# CGScale.net
KiCad netlist of a schematic drawn in EAGLE
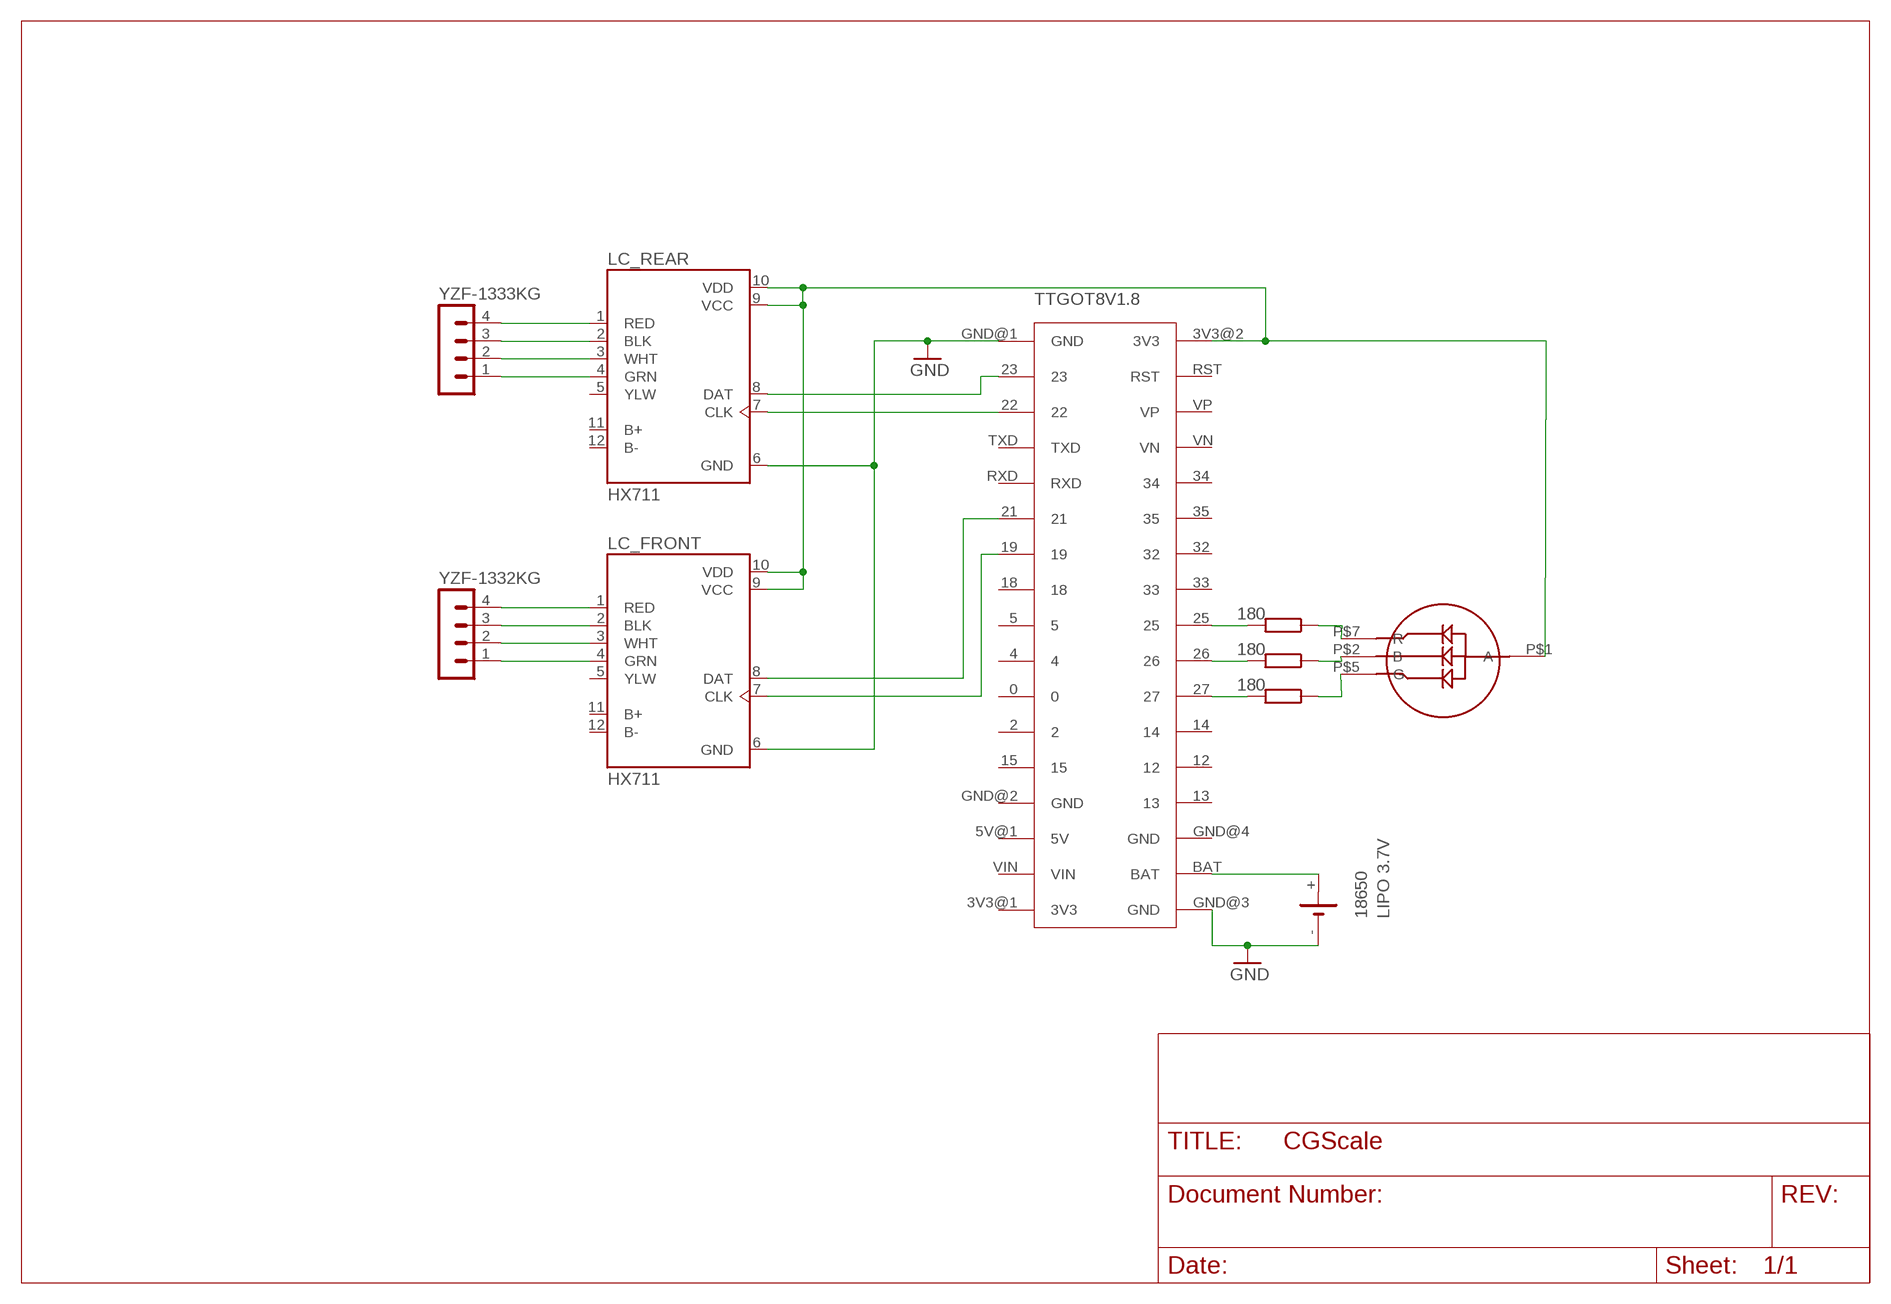
[diagram p0: schematic, sheet 1]

(export (version "E")
  (design (tool "Eeschema 10.0.6"))
  (components
    (comp (ref "18650")
      (value "LIPO 3.7V")
      (footprint "eagle-import:SL-150-1_2AA_PR")
      (libsource (lib "eagle-import") (part "SL-150-1/2AA/PR"))
    )
    (comp (ref "LC_FRONT")
      (value "HX711")
      (footprint "eagle-import:SPARKFUN_SEN-13879")
      (fields (field (name "MF") "SparkFun") (field (name "MP") "SEN-13879"))
      (libsource (lib "eagle-import") (part "SEN-13879"))
    )
    (comp (ref "LC_REAR")
      (value "HX711")
      (footprint "eagle-import:SPARKFUN_SEN-13879")
      (fields (field (name "MF") "SparkFun") (field (name "MP") "SEN-13879"))
      (libsource (lib "eagle-import") (part "SEN-13879"))
    )
    (comp (ref "RGB_LED")
      (value "LED-4_PIN")
      (footprint "eagle-import:LED-4_PIN")
      (libsource (lib "eagle-import") (part "LED-4_PIN"))
    )
    (comp (ref "TTGOT8V1.8")
      (value "TTGO-T8_V18")
      (footprint "eagle-import:TTGO-T8_V18")
      (libsource (lib "eagle-import") (part "TTGO-T8_V18"))
    )
    (comp (ref "YZF-1332KG")
      (value "MA04-1")
      (footprint "eagle-import:MA04-1")
      (libsource (lib "eagle-import") (part "MA04-1"))
    )
    (comp (ref "YZF-1333KG")
      (value "MA04-1")
      (footprint "eagle-import:MA04-1")
      (libsource (lib "eagle-import") (part "MA04-1"))
    )
  )
  (nets
    (net (code "1") (name "GND") (class "Default")
      (node (ref "18650") (pin "-") (pinfunction "-_-") (pintype "passive"))
      (node (ref "LC_FRONT") (pin "6") (pinfunction "GND_6") (pintype "power_in"))
      (node (ref "LC_REAR") (pin "6") (pinfunction "GND_6") (pintype "power_in"))
      (node (ref "TTGOT8V1.8") (pin "GND@1") (pinfunction "GND_GND@1") (pintype "bidirectional"))
      (node (ref "TTGOT8V1.8") (pin "GND@3") (pinfunction "GND_GND@3") (pintype "bidirectional"))
    )
    (net (code "2") (name "Net-(18650-Pad+)") (class "Default")
      (node (ref "18650") (pin "+") (pinfunction "+_+") (pintype "passive"))
      (node (ref "TTGOT8V1.8") (pin "BAT") (pinfunction "BAT_BAT") (pintype "bidirectional"))
    )
    (net (code "3") (name "Net-(LC_FRONT-BLK)") (class "Default")
      (node (ref "LC_FRONT") (pin "2") (pinfunction "BLK_2") (pintype "bidirectional"))
      (node (ref "YZF-1332KG") (pin "3") (pinfunction "3_3") (pintype "passive"))
    )
    (net (code "4") (name "Net-(LC_FRONT-CLK)") (class "Default")
      (node (ref "LC_FRONT") (pin "7") (pinfunction "CLK_7") (pintype "input"))
      (node (ref "TTGOT8V1.8") (pin "19") (pinfunction "19_19") (pintype "bidirectional"))
    )
    (net (code "5") (name "Net-(LC_FRONT-DAT)") (class "Default")
      (node (ref "LC_FRONT") (pin "8") (pinfunction "DAT_8") (pintype "output"))
      (node (ref "TTGOT8V1.8") (pin "21") (pinfunction "21_21") (pintype "bidirectional"))
    )
    (net (code "6") (name "Net-(LC_FRONT-GRN)") (class "Default")
      (node (ref "LC_FRONT") (pin "4") (pinfunction "GRN_4") (pintype "input"))
      (node (ref "YZF-1332KG") (pin "1") (pinfunction "1_1") (pintype "passive"))
    )
    (net (code "7") (name "Net-(LC_FRONT-RED)") (class "Default")
      (node (ref "LC_FRONT") (pin "1") (pinfunction "RED_1") (pintype "bidirectional"))
      (node (ref "YZF-1332KG") (pin "4") (pinfunction "4_4") (pintype "passive"))
    )
    (net (code "8") (name "Net-(LC_FRONT-VCC)") (class "Default")
      (node (ref "LC_FRONT") (pin "10") (pinfunction "VDD_10") (pintype "power_in"))
      (node (ref "LC_FRONT") (pin "9") (pinfunction "VCC_9") (pintype "power_in"))
      (node (ref "LC_REAR") (pin "10") (pinfunction "VDD_10") (pintype "power_in"))
      (node (ref "LC_REAR") (pin "9") (pinfunction "VCC_9") (pintype "power_in"))
      (node (ref "RGB_LED") (pin "P$1") (pinfunction "A_P$1") (pintype "bidirectional"))
      (node (ref "TTGOT8V1.8") (pin "3V3@2") (pinfunction "3V3_3V3@2") (pintype "bidirectional"))
    )
    (net (code "9") (name "Net-(LC_FRONT-WHT)") (class "Default")
      (node (ref "LC_FRONT") (pin "3") (pinfunction "WHT_3") (pintype "input"))
      (node (ref "YZF-1332KG") (pin "2") (pinfunction "2_2") (pintype "passive"))
    )
    (net (code "10") (name "Net-(LC_REAR-BLK)") (class "Default")
      (node (ref "LC_REAR") (pin "2") (pinfunction "BLK_2") (pintype "bidirectional"))
      (node (ref "YZF-1333KG") (pin "3") (pinfunction "3_3") (pintype "passive"))
    )
    (net (code "11") (name "Net-(LC_REAR-CLK)") (class "Default")
      (node (ref "LC_REAR") (pin "7") (pinfunction "CLK_7") (pintype "input"))
      (node (ref "TTGOT8V1.8") (pin "22") (pinfunction "22_22") (pintype "bidirectional"))
    )
    (net (code "12") (name "Net-(LC_REAR-DAT)") (class "Default")
      (node (ref "LC_REAR") (pin "8") (pinfunction "DAT_8") (pintype "output"))
      (node (ref "TTGOT8V1.8") (pin "23") (pinfunction "23_23") (pintype "bidirectional"))
    )
    (net (code "13") (name "Net-(LC_REAR-GRN)") (class "Default")
      (node (ref "LC_REAR") (pin "4") (pinfunction "GRN_4") (pintype "input"))
      (node (ref "YZF-1333KG") (pin "1") (pinfunction "1_1") (pintype "passive"))
    )
    (net (code "14") (name "Net-(LC_REAR-RED)") (class "Default")
      (node (ref "LC_REAR") (pin "1") (pinfunction "RED_1") (pintype "bidirectional"))
      (node (ref "YZF-1333KG") (pin "4") (pinfunction "4_4") (pintype "passive"))
    )
    (net (code "15") (name "Net-(LC_REAR-WHT)") (class "Default")
      (node (ref "LC_REAR") (pin "3") (pinfunction "WHT_3") (pintype "input"))
      (node (ref "YZF-1333KG") (pin "2") (pinfunction "2_2") (pintype "passive"))
    )
    (net (code "16") (name "unconnected-(LC_FRONT-B+-Pad11)") (class "Default")
      (node (ref "LC_FRONT") (pin "11") (pinfunction "B+_11") (pintype "input"))
    )
    (net (code "17") (name "unconnected-(LC_FRONT-B--Pad12)") (class "Default")
      (node (ref "LC_FRONT") (pin "12") (pinfunction "B-_12") (pintype "input"))
    )
    (net (code "18") (name "unconnected-(LC_FRONT-YLW-Pad5)") (class "Default")
      (node (ref "LC_FRONT") (pin "5") (pinfunction "YLW_5") (pintype "bidirectional"))
    )
    (net (code "19") (name "unconnected-(LC_REAR-B+-Pad11)") (class "Default")
      (node (ref "LC_REAR") (pin "11") (pinfunction "B+_11") (pintype "input"))
    )
    (net (code "20") (name "unconnected-(LC_REAR-B--Pad12)") (class "Default")
      (node (ref "LC_REAR") (pin "12") (pinfunction "B-_12") (pintype "input"))
    )
    (net (code "21") (name "unconnected-(LC_REAR-YLW-Pad5)") (class "Default")
      (node (ref "LC_REAR") (pin "5") (pinfunction "YLW_5") (pintype "bidirectional"))
    )
    (net (code "22") (name "unconnected-(RGB_LED-B-PadP$2)") (class "Default")
      (node (ref "RGB_LED") (pin "P$2") (pinfunction "B_P$2") (pintype "bidirectional"))
    )
    (net (code "23") (name "unconnected-(RGB_LED-G-PadP$5)") (class "Default")
      (node (ref "RGB_LED") (pin "P$5") (pinfunction "G_P$5") (pintype "bidirectional"))
    )
    (net (code "24") (name "unconnected-(RGB_LED-R-PadP$7)") (class "Default")
      (node (ref "RGB_LED") (pin "P$7") (pinfunction "R_P$7") (pintype "bidirectional"))
    )
    (net (code "25") (name "unconnected-(TTGOT8V1.8-3V3-Pad3V3@1)") (class "Default")
      (node (ref "TTGOT8V1.8") (pin "3V3@1") (pinfunction "3V3_3V3@1") (pintype "bidirectional"))
    )
    (net (code "26") (name "unconnected-(TTGOT8V1.8-5V-Pad5V@1)") (class "Default")
      (node (ref "TTGOT8V1.8") (pin "5V@1") (pinfunction "5V_5V@1") (pintype "bidirectional"))
    )
    (net (code "27") (name "unconnected-(TTGOT8V1.8-GND-PadGND@2)") (class "Default")
      (node (ref "TTGOT8V1.8") (pin "GND@2") (pinfunction "GND_GND@2") (pintype "bidirectional"))
    )
    (net (code "28") (name "unconnected-(TTGOT8V1.8-GND-PadGND@4)") (class "Default")
      (node (ref "TTGOT8V1.8") (pin "GND@4") (pinfunction "GND_GND@4") (pintype "bidirectional"))
    )
    (net (code "29") (name "unconnected-(TTGOT8V1.8-Pad0)") (class "Default")
      (node (ref "TTGOT8V1.8") (pin "0") (pinfunction "0_0") (pintype "bidirectional"))
    )
    (net (code "30") (name "unconnected-(TTGOT8V1.8-Pad2)") (class "Default")
      (node (ref "TTGOT8V1.8") (pin "2") (pinfunction "2_2") (pintype "bidirectional"))
    )
    (net (code "31") (name "unconnected-(TTGOT8V1.8-Pad4)") (class "Default")
      (node (ref "TTGOT8V1.8") (pin "4") (pinfunction "4_4") (pintype "bidirectional"))
    )
    (net (code "32") (name "unconnected-(TTGOT8V1.8-Pad5)") (class "Default")
      (node (ref "TTGOT8V1.8") (pin "5") (pinfunction "5_5") (pintype "bidirectional"))
    )
    (net (code "33") (name "unconnected-(TTGOT8V1.8-Pad12)") (class "Default")
      (node (ref "TTGOT8V1.8") (pin "12") (pinfunction "12_12") (pintype "bidirectional"))
    )
    (net (code "34") (name "unconnected-(TTGOT8V1.8-Pad13)") (class "Default")
      (node (ref "TTGOT8V1.8") (pin "13") (pinfunction "13_13") (pintype "bidirectional"))
    )
    (net (code "35") (name "unconnected-(TTGOT8V1.8-Pad14)") (class "Default")
      (node (ref "TTGOT8V1.8") (pin "14") (pinfunction "14_14") (pintype "bidirectional"))
    )
    (net (code "36") (name "unconnected-(TTGOT8V1.8-Pad15)") (class "Default")
      (node (ref "TTGOT8V1.8") (pin "15") (pinfunction "15_15") (pintype "bidirectional"))
    )
    (net (code "37") (name "unconnected-(TTGOT8V1.8-Pad18)") (class "Default")
      (node (ref "TTGOT8V1.8") (pin "18") (pinfunction "18_18") (pintype "bidirectional"))
    )
    (net (code "38") (name "unconnected-(TTGOT8V1.8-Pad25)") (class "Default")
      (node (ref "TTGOT8V1.8") (pin "25") (pinfunction "25_25") (pintype "bidirectional"))
    )
    (net (code "39") (name "unconnected-(TTGOT8V1.8-Pad26)") (class "Default")
      (node (ref "TTGOT8V1.8") (pin "26") (pinfunction "26_26") (pintype "bidirectional"))
    )
    (net (code "40") (name "unconnected-(TTGOT8V1.8-Pad27)") (class "Default")
      (node (ref "TTGOT8V1.8") (pin "27") (pinfunction "27_27") (pintype "bidirectional"))
    )
    (net (code "41") (name "unconnected-(TTGOT8V1.8-Pad32)") (class "Default")
      (node (ref "TTGOT8V1.8") (pin "32") (pinfunction "32_32") (pintype "bidirectional"))
    )
    (net (code "42") (name "unconnected-(TTGOT8V1.8-Pad33)") (class "Default")
      (node (ref "TTGOT8V1.8") (pin "33") (pinfunction "33_33") (pintype "bidirectional"))
    )
    (net (code "43") (name "unconnected-(TTGOT8V1.8-Pad34)") (class "Default")
      (node (ref "TTGOT8V1.8") (pin "34") (pinfunction "34_34") (pintype "bidirectional"))
    )
    (net (code "44") (name "unconnected-(TTGOT8V1.8-Pad35)") (class "Default")
      (node (ref "TTGOT8V1.8") (pin "35") (pinfunction "35_35") (pintype "bidirectional"))
    )
    (net (code "45") (name "unconnected-(TTGOT8V1.8-PadRST)") (class "Default")
      (node (ref "TTGOT8V1.8") (pin "RST") (pinfunction "RST_RST") (pintype "bidirectional"))
    )
    (net (code "46") (name "unconnected-(TTGOT8V1.8-PadRXD)") (class "Default")
      (node (ref "TTGOT8V1.8") (pin "RXD") (pinfunction "RXD_RXD") (pintype "bidirectional"))
    )
    (net (code "47") (name "unconnected-(TTGOT8V1.8-PadTXD)") (class "Default")
      (node (ref "TTGOT8V1.8") (pin "TXD") (pinfunction "TXD_TXD") (pintype "bidirectional"))
    )
    (net (code "48") (name "unconnected-(TTGOT8V1.8-PadVIN)") (class "Default")
      (node (ref "TTGOT8V1.8") (pin "VIN") (pinfunction "VIN_VIN") (pintype "bidirectional"))
    )
    (net (code "49") (name "unconnected-(TTGOT8V1.8-PadVN)") (class "Default")
      (node (ref "TTGOT8V1.8") (pin "VN") (pinfunction "VN_VN") (pintype "bidirectional"))
    )
    (net (code "50") (name "unconnected-(TTGOT8V1.8-PadVP)") (class "Default")
      (node (ref "TTGOT8V1.8") (pin "VP") (pinfunction "VP_VP") (pintype "bidirectional"))
    )
  )
)
